# ShEj4.net
KiCad netlist of a schematic drawn in Altium Designer
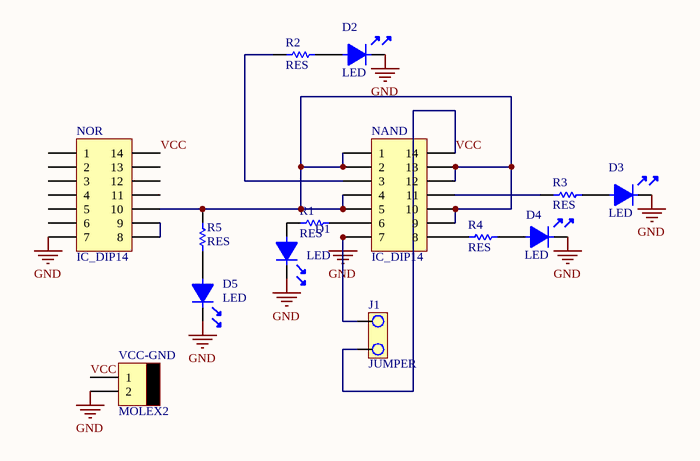
[diagram p0: ShEj4.SchDoc]

(export (version "E")
  (design (tool "Eeschema 10.0.6"))
  (components
    (comp (ref "D1") (value "LED") (footprint "LED3") (libsource (lib "LIBEBAL") (part "LED")))
    (comp (ref "D2") (value "LED") (footprint "LED3") (libsource (lib "LIBEBAL") (part "LED")))
    (comp (ref "D3") (value "LED") (footprint "LED3") (libsource (lib "LIBEBAL") (part "LED")))
    (comp (ref "D4") (value "LED") (footprint "LED3") (libsource (lib "LIBEBAL") (part "LED")))
    (comp (ref "D5") (value "LED") (footprint "LED3") (libsource (lib "LIBEBAL") (part "LED")))
    (comp (ref "J1") (value "JUMPER") (footprint "JUMPER2") (libsource (lib "LIBEBAL") (part "JUMPER")))
    (comp (ref "NAND") (value "IC_DIP14") (footprint "DIP14") (libsource (lib "LIBEBAL") (part "IC_DIP14")))
    (comp (ref "NOR") (value "IC_DIP14") (footprint "DIP14") (libsource (lib "LIBEBAL") (part "IC_DIP14")))
    (comp (ref "R1") (value "RES") (footprint "RES400") (libsource (lib "LIBEBAL") (part "RES")))
    (comp (ref "R2") (value "RES") (footprint "RES400") (libsource (lib "LIBEBAL") (part "RES")))
    (comp (ref "R3") (value "RES") (footprint "RES400") (libsource (lib "LIBEBAL") (part "RES")))
    (comp (ref "R4") (value "RES") (footprint "RES400") (libsource (lib "LIBEBAL") (part "RES")))
    (comp (ref "R5") (value "RES") (footprint "RES400") (libsource (lib "LIBEBAL") (part "RES")))
    (comp (ref "VCC-GND") (value "MOLEX2") (footprint "MOLEX2") (libsource (lib "LIBEBAL") (part "MOLEX2")))
  )
  (nets
    (net (code "1") (name "/VCC") (class "Default")
      (node (ref "J1") (pin "1") (pinfunction "1_1") (pintype "passive"))
      (node (ref "NAND") (pin "14") (pinfunction "14_14") (pintype "passive"))
      (node (ref "NOR") (pin "14") (pinfunction "14_14") (pintype "passive"))
      (node (ref "VCC-GND") (pin "1") (pinfunction "1_1") (pintype "passive"))
    )
    (net (code "2") (name "GND") (class "Default")
      (node (ref "D1") (pin "2") (pinfunction "2_2") (pintype "passive"))
      (node (ref "D2") (pin "2") (pinfunction "2_2") (pintype "passive"))
      (node (ref "D3") (pin "2") (pinfunction "2_2") (pintype "passive"))
      (node (ref "D4") (pin "2") (pinfunction "2_2") (pintype "passive"))
      (node (ref "D5") (pin "2") (pinfunction "2_2") (pintype "passive"))
      (node (ref "J1") (pin "2") (pinfunction "2_2") (pintype "passive"))
      (node (ref "NAND") (pin "7") (pinfunction "7_7") (pintype "passive"))
      (node (ref "NOR") (pin "7") (pinfunction "7_7") (pintype "passive"))
      (node (ref "VCC-GND") (pin "2") (pinfunction "2_2") (pintype "passive"))
    )
    (net (code "3") (name "Net-(D1-Pad1)") (class "Default")
      (node (ref "D1") (pin "1") (pinfunction "1_1") (pintype "passive"))
      (node (ref "R1") (pin "1") (pinfunction "1_1") (pintype "passive"))
    )
    (net (code "4") (name "Net-(D2-Pad1)") (class "Default")
      (node (ref "D2") (pin "1") (pinfunction "1_1") (pintype "passive"))
      (node (ref "R2") (pin "2") (pinfunction "2_2") (pintype "passive"))
    )
    (net (code "5") (name "Net-(D3-Pad1)") (class "Default")
      (node (ref "D3") (pin "1") (pinfunction "1_1") (pintype "passive"))
      (node (ref "R3") (pin "2") (pinfunction "2_2") (pintype "passive"))
    )
    (net (code "6") (name "Net-(D4-Pad1)") (class "Default")
      (node (ref "D4") (pin "1") (pinfunction "1_1") (pintype "passive"))
      (node (ref "R4") (pin "2") (pinfunction "2_2") (pintype "passive"))
    )
    (net (code "7") (name "Net-(D5-Pad1)") (class "Default")
      (node (ref "D5") (pin "1") (pinfunction "1_1") (pintype "passive"))
      (node (ref "R5") (pin "1") (pinfunction "1_1") (pintype "passive"))
    )
    (net (code "8") (name "Net-(NAND-Pad1)") (class "Default")
      (node (ref "NAND") (pin "1") (pinfunction "1_1") (pintype "passive"))
      (node (ref "NAND") (pin "10") (pinfunction "10_10") (pintype "passive"))
      (node (ref "NAND") (pin "12") (pinfunction "12_12") (pintype "passive"))
      (node (ref "NAND") (pin "13") (pinfunction "13_13") (pintype "passive"))
      (node (ref "NAND") (pin "2") (pinfunction "2_2") (pintype "passive"))
      (node (ref "NAND") (pin "4") (pinfunction "4_4") (pintype "passive"))
      (node (ref "NAND") (pin "5") (pinfunction "5_5") (pintype "passive"))
      (node (ref "NAND") (pin "9") (pinfunction "9_9") (pintype "passive"))
      (node (ref "NOR") (pin "10") (pinfunction "10_10") (pintype "passive"))
      (node (ref "R5") (pin "2") (pinfunction "2_2") (pintype "passive"))
    )
    (net (code "9") (name "Net-(NAND-Pad3)") (class "Default")
      (node (ref "NAND") (pin "3") (pinfunction "3_3") (pintype "passive"))
      (node (ref "R2") (pin "1") (pinfunction "1_1") (pintype "passive"))
    )
    (net (code "10") (name "Net-(NAND-Pad6)") (class "Default")
      (node (ref "NAND") (pin "6") (pinfunction "6_6") (pintype "passive"))
      (node (ref "R1") (pin "2") (pinfunction "2_2") (pintype "passive"))
    )
    (net (code "11") (name "Net-(NAND-Pad8)") (class "Default")
      (node (ref "NAND") (pin "8") (pinfunction "8_8") (pintype "passive"))
      (node (ref "R4") (pin "1") (pinfunction "1_1") (pintype "passive"))
    )
    (net (code "12") (name "Net-(NAND-Pad11)") (class "Default")
      (node (ref "NAND") (pin "11") (pinfunction "11_11") (pintype "passive"))
      (node (ref "R3") (pin "1") (pinfunction "1_1") (pintype "passive"))
    )
    (net (code "13") (name "Net-(NOR-Pad8)") (class "Default")
      (node (ref "NOR") (pin "8") (pinfunction "8_8") (pintype "passive"))
      (node (ref "NOR") (pin "9") (pinfunction "9_9") (pintype "passive"))
    )
    (net (code "14") (name "unconnected-(NOR-Pad1)") (class "Default")
      (node (ref "NOR") (pin "1") (pinfunction "1_1") (pintype "passive"))
    )
    (net (code "15") (name "unconnected-(NOR-Pad2)") (class "Default")
      (node (ref "NOR") (pin "2") (pinfunction "2_2") (pintype "passive"))
    )
    (net (code "16") (name "unconnected-(NOR-Pad3)") (class "Default")
      (node (ref "NOR") (pin "3") (pinfunction "3_3") (pintype "passive"))
    )
    (net (code "17") (name "unconnected-(NOR-Pad4)") (class "Default")
      (node (ref "NOR") (pin "4") (pinfunction "4_4") (pintype "passive"))
    )
    (net (code "18") (name "unconnected-(NOR-Pad5)") (class "Default")
      (node (ref "NOR") (pin "5") (pinfunction "5_5") (pintype "passive"))
    )
    (net (code "19") (name "unconnected-(NOR-Pad6)") (class "Default")
      (node (ref "NOR") (pin "6") (pinfunction "6_6") (pintype "passive"))
    )
    (net (code "20") (name "unconnected-(NOR-Pad11)") (class "Default")
      (node (ref "NOR") (pin "11") (pinfunction "11_11") (pintype "passive"))
    )
    (net (code "21") (name "unconnected-(NOR-Pad12)") (class "Default")
      (node (ref "NOR") (pin "12") (pinfunction "12_12") (pintype "passive"))
    )
    (net (code "22") (name "unconnected-(NOR-Pad13)") (class "Default")
      (node (ref "NOR") (pin "13") (pinfunction "13_13") (pintype "passive"))
    )
  )
)
